# design.net
KiCad netlist of a schematic drawn in EasyEDA Pro
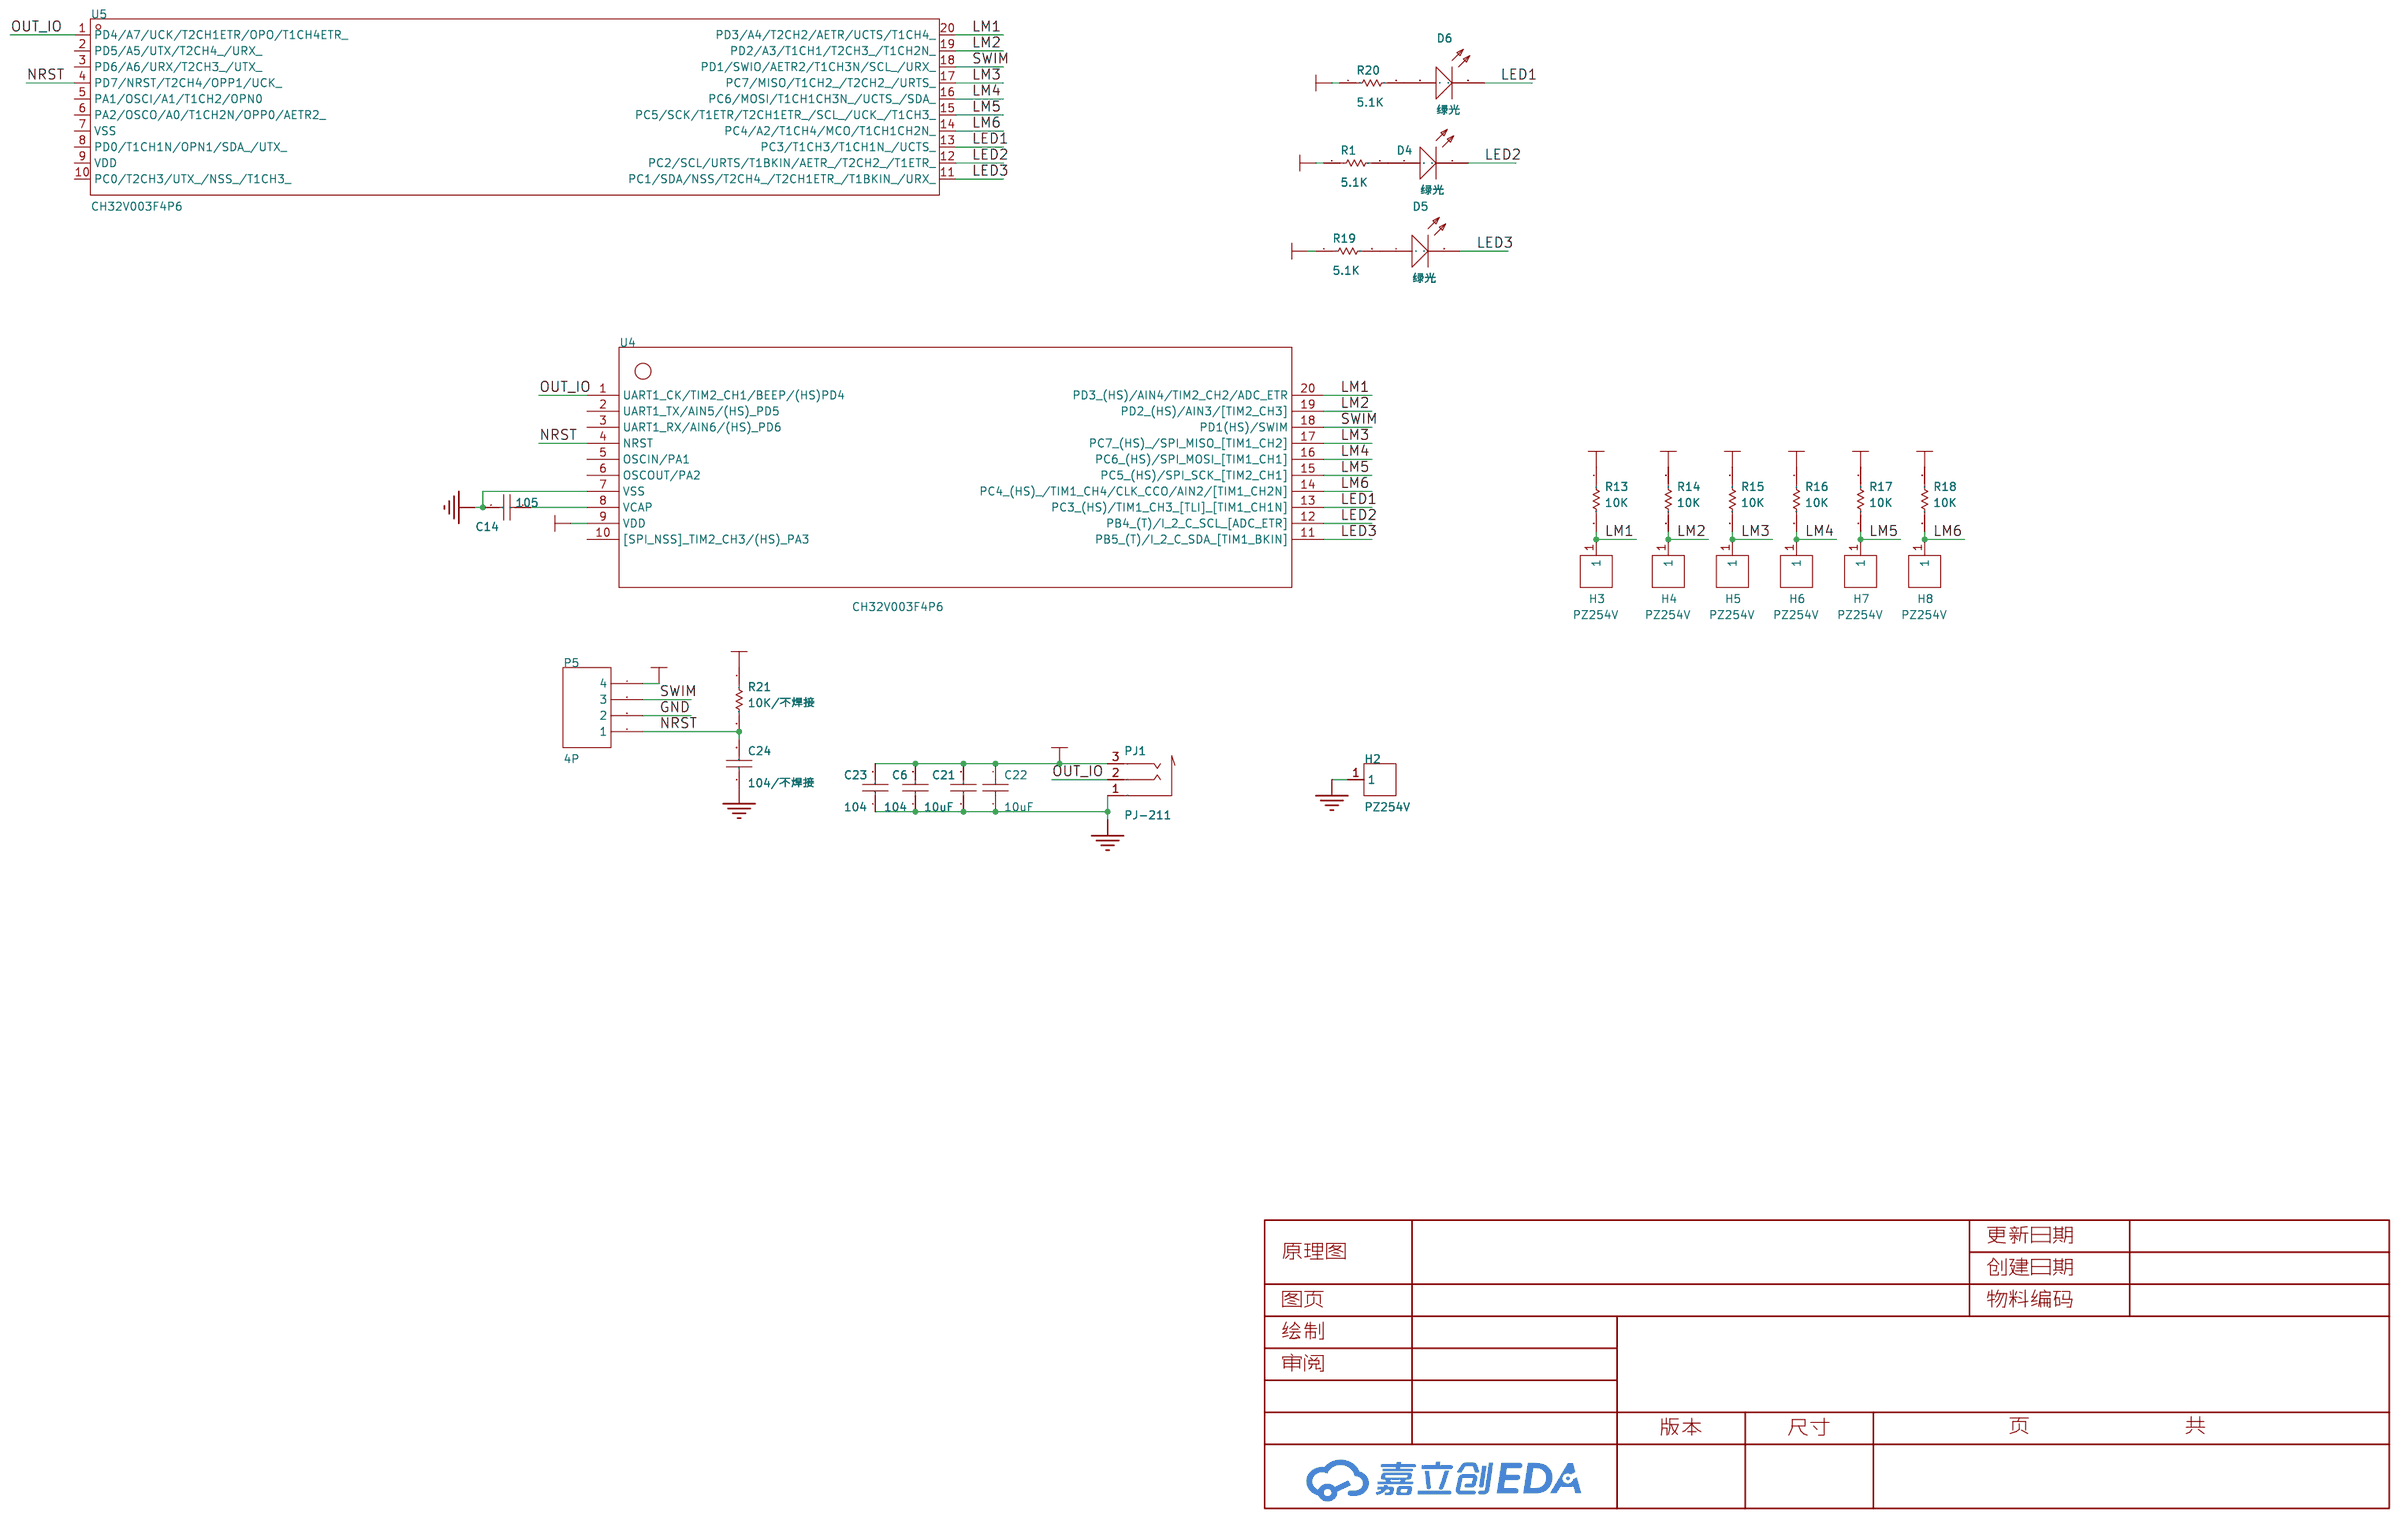
[diagram p0: schematic sheet]

(export (version "E")
  (design (tool "Eeschema 10.0.6"))
  (components
    (comp (ref "C6")
      (value "104")
      (footprint "easyedapro:0603C")
      (description "Capacitor (Semiconductor SIM Model)")
      (libsource (lib "easyedapro") (part "Cap Semi"))
    )
    (comp (ref "C14")
      (value "105")
      (footprint "easyedapro:0603C")
      (description "Capacitor (Semiconductor SIM Model)")
      (libsource (lib "easyedapro") (part "Cap Semi"))
    )
    (comp (ref "C21") (value "10uF") (libsource (lib "easyedapro") (part "CAP")))
    (comp (ref "C22") (value "10uF") (libsource (lib "easyedapro") (part "CAP")))
    (comp (ref "C23")
      (value "104")
      (footprint "easyedapro:0603C")
      (description "Capacitor (Semiconductor SIM Model)")
      (libsource (lib "easyedapro") (part "Cap Semi"))
    )
    (comp (ref "C24")
      (value "104/不焊接")
      (footprint "easyedapro:0603C")
      (description "Capacitor (Semiconductor SIM Model)")
      (libsource (lib "easyedapro") (part "Cap Semi"))
    )
    (comp (ref "D4")
      (value "绿光")
      (footprint "easyedapro:0603LED")
      (libsource (lib "easyedapro") (part "LED"))
    )
    (comp (ref "D5")
      (value "绿光")
      (footprint "easyedapro:0603LED")
      (libsource (lib "easyedapro") (part "LED"))
    )
    (comp (ref "D6")
      (value "绿光")
      (footprint "easyedapro:0603LED")
      (libsource (lib "easyedapro") (part "LED"))
    )
    (comp (ref "H2")
      (value "PZ254V")
      (footprint "easyedapro:HDR-TH_1P-PZ254V-11-01P-YL")
      (description "排针2.54mm间距 直插 1x01位 黄色胶芯")
      (fields (field (name "Manufacturer") "XFCN(兴飞)"))
      (libsource (lib "easyedapro") (part "PZ254V-11-01P-YL"))
    )
    (comp (ref "H3")
      (value "PZ254V")
      (footprint "easyedapro:HDR-TH_1P-PZ254V-11-01P-YL")
      (description "排针2.54mm间距 直插 1x01位 黄色胶芯")
      (fields (field (name "Manufacturer") "XFCN(兴飞)"))
      (libsource (lib "easyedapro") (part "PZ254V-11-01P-YL"))
    )
    (comp (ref "H4")
      (value "PZ254V")
      (footprint "easyedapro:HDR-TH_1P-PZ254V-11-01P-YL")
      (description "排针2.54mm间距 直插 1x01位 黄色胶芯")
      (fields (field (name "Manufacturer") "XFCN(兴飞)"))
      (libsource (lib "easyedapro") (part "PZ254V-11-01P-YL"))
    )
    (comp (ref "H5")
      (value "PZ254V")
      (footprint "easyedapro:HDR-TH_1P-PZ254V-11-01P-YL")
      (description "排针2.54mm间距 直插 1x01位 黄色胶芯")
      (fields (field (name "Manufacturer") "XFCN(兴飞)"))
      (libsource (lib "easyedapro") (part "PZ254V-11-01P-YL"))
    )
    (comp (ref "H6")
      (value "PZ254V")
      (footprint "easyedapro:HDR-TH_1P-PZ254V-11-01P-YL")
      (description "排针2.54mm间距 直插 1x01位 黄色胶芯")
      (fields (field (name "Manufacturer") "XFCN(兴飞)"))
      (libsource (lib "easyedapro") (part "PZ254V-11-01P-YL"))
    )
    (comp (ref "H7")
      (value "PZ254V")
      (footprint "easyedapro:HDR-TH_1P-PZ254V-11-01P-YL")
      (description "排针2.54mm间距 直插 1x01位 黄色胶芯")
      (fields (field (name "Manufacturer") "XFCN(兴飞)"))
      (libsource (lib "easyedapro") (part "PZ254V-11-01P-YL"))
    )
    (comp (ref "H8")
      (value "PZ254V")
      (footprint "easyedapro:HDR-TH_1P-PZ254V-11-01P-YL")
      (description "排针2.54mm间距 直插 1x01位 黄色胶芯")
      (fields (field (name "Manufacturer") "XFCN(兴飞)"))
      (libsource (lib "easyedapro") (part "PZ254V-11-01P-YL"))
    )
    (comp (ref "P5") (value "4P") (libsource (lib "easyedapro") (part "4P")))
    (comp (ref "PJ1")
      (value "PJ-211")
      (footprint "easyedapro:AUDIO-TH_PJ-211")
      (description "连接器类型:2.5mm耳机座;额定电流:500mA;额定电压:30V;触头材质:铜;触头镀层:银;工作温度范围:-30°C~+70°C;")
      (fields (field (name "Manufacturer") "SHOU HAN(首韩)"))
      (libsource (lib "easyedapro") (part "PJ-211"))
    )
    (comp (ref "R1")
      (value "5.1K")
      (footprint "easyedapro:0603R")
      (description "Resistor")
      (libsource (lib "easyedapro") (part "RES"))
    )
    (comp (ref "R13")
      (value "10K")
      (footprint "easyedapro:0603R")
      (description "Resistor")
      (libsource (lib "easyedapro") (part "RES"))
    )
    (comp (ref "R14")
      (value "10K")
      (footprint "easyedapro:0603R")
      (description "Resistor")
      (libsource (lib "easyedapro") (part "RES"))
    )
    (comp (ref "R15")
      (value "10K")
      (footprint "easyedapro:0603R")
      (description "Resistor")
      (libsource (lib "easyedapro") (part "RES"))
    )
    (comp (ref "R16")
      (value "10K")
      (footprint "easyedapro:0603R")
      (description "Resistor")
      (libsource (lib "easyedapro") (part "RES"))
    )
    (comp (ref "R17")
      (value "10K")
      (footprint "easyedapro:0603R")
      (description "Resistor")
      (libsource (lib "easyedapro") (part "RES"))
    )
    (comp (ref "R18")
      (value "10K")
      (footprint "easyedapro:0603R")
      (description "Resistor")
      (libsource (lib "easyedapro") (part "RES"))
    )
    (comp (ref "R19")
      (value "5.1K")
      (footprint "easyedapro:0603R")
      (description "Resistor")
      (libsource (lib "easyedapro") (part "RES"))
    )
    (comp (ref "R20")
      (value "5.1K")
      (footprint "easyedapro:0603R")
      (description "Resistor")
      (libsource (lib "easyedapro") (part "RES"))
    )
    (comp (ref "R21")
      (value "10K/不焊接")
      (footprint "easyedapro:0603R")
      (description "Resistor")
      (libsource (lib "easyedapro") (part "RES"))
    )
    (comp (ref "U4")
      (value "CH32V003F4P6")
      (footprint "easyedapro:TSSOP-20_L6.5-W4.4-P0.65-LS6.4-BL")
      (description "CPU内核:STM8;主频（MAX):16MHz;工作电压:2.95V~ 5.5V;")
      (fields (field (name "Manufacturer") "ST(意法半导体)"))
      (libsource (lib "easyedapro") (part "STM8S003F3P6TR"))
    )
    (comp (ref "U5")
      (value "CH32V003F4P6")
      (footprint "easyedapro:TSSOP-20_L6.5-W4.4-P0.65-LS6.4-BL")
      (fields (field (name "Manufacturer") "WCH(南京沁恒)"))
      (libsource (lib "easyedapro") (part "CH32V003F4P6"))
    )
  )
  (nets
    (net (code "1") (name "/LED1") (class "Default")
      (node (ref "D6") (pin "2") (pinfunction "2_2") (pintype "unspecified"))
      (node (ref "U4") (pin "13") (pinfunction "PC3_(HS)/TIM1_CH3_[TLI]_[TIM1_CH1N]_13") (pintype "input"))
      (node (ref "U5") (pin "13") (pinfunction "PC3/T1CH3/T1CH1N_/UCTS__13") (pintype "unspecified"))
    )
    (net (code "2") (name "/LED2") (class "Default")
      (node (ref "D4") (pin "2") (pinfunction "2_2") (pintype "unspecified"))
      (node (ref "U4") (pin "12") (pinfunction "PB4_(T)/I_2_C_SCL_[ADC_ETR]_12") (pintype "input"))
      (node (ref "U5") (pin "12") (pinfunction "PC2/SCL/URTS/T1BKIN/AETR_/T2CH2_/T1ETR__12") (pintype "unspecified"))
    )
    (net (code "3") (name "/LED3") (class "Default")
      (node (ref "D5") (pin "2") (pinfunction "2_2") (pintype "unspecified"))
      (node (ref "U4") (pin "11") (pinfunction "PB5_(T)/I_2_C_SDA_[TIM1_BKIN]_11") (pintype "input"))
      (node (ref "U5") (pin "11") (pinfunction "PC1/SDA/NSS/T2CH4_/T2CH1ETR_/T1BKIN_/URX__11") (pintype "unspecified"))
    )
    (net (code "4") (name "/LM1") (class "Default")
      (node (ref "H3") (pin "1") (pinfunction "1_1") (pintype "unspecified"))
      (node (ref "R13") (pin "2") (pinfunction "2_2") (pintype "unspecified"))
      (node (ref "U4") (pin "20") (pinfunction "PD3_(HS)/AIN4/TIM2_CH2/ADC_ETR_20") (pintype "input"))
      (node (ref "U5") (pin "20") (pinfunction "PD3/A4/T2CH2/AETR/UCTS/T1CH4__20") (pintype "unspecified"))
    )
    (net (code "5") (name "/LM2") (class "Default")
      (node (ref "H4") (pin "1") (pinfunction "1_1") (pintype "unspecified"))
      (node (ref "R14") (pin "2") (pinfunction "2_2") (pintype "unspecified"))
      (node (ref "U4") (pin "19") (pinfunction "PD2_(HS)/AIN3/[TIM2_CH3]_19") (pintype "input"))
      (node (ref "U5") (pin "19") (pinfunction "PD2/A3/T1CH1/T2CH3_/T1CH2N__19") (pintype "unspecified"))
    )
    (net (code "6") (name "/LM3") (class "Default")
      (node (ref "H5") (pin "1") (pinfunction "1_1") (pintype "unspecified"))
      (node (ref "R15") (pin "2") (pinfunction "2_2") (pintype "unspecified"))
      (node (ref "U4") (pin "17") (pinfunction "PC7_(HS)_/SPI_MISO_[TIM1_CH2]_17") (pintype "input"))
      (node (ref "U5") (pin "17") (pinfunction "PC7/MISO/T1CH2_/T2CH2_/URTS__17") (pintype "unspecified"))
    )
    (net (code "7") (name "/LM4") (class "Default")
      (node (ref "H6") (pin "1") (pinfunction "1_1") (pintype "unspecified"))
      (node (ref "R16") (pin "2") (pinfunction "2_2") (pintype "unspecified"))
      (node (ref "U4") (pin "16") (pinfunction "PC6_(HS)/SPI_MOSI_[TIM1_CH1]_16") (pintype "input"))
      (node (ref "U5") (pin "16") (pinfunction "PC6/MOSI/T1CH1CH3N_/UCTS_/SDA__16") (pintype "unspecified"))
    )
    (net (code "8") (name "/LM5") (class "Default")
      (node (ref "H7") (pin "1") (pinfunction "1_1") (pintype "unspecified"))
      (node (ref "R17") (pin "2") (pinfunction "2_2") (pintype "unspecified"))
      (node (ref "U4") (pin "15") (pinfunction "PC5_(HS)/SPI_SCK_[TIM2_CH1]_15") (pintype "input"))
      (node (ref "U5") (pin "15") (pinfunction "PC5/SCK/T1ETR/T2CH1ETR_/SCL_/UCK_/T1CH3__15") (pintype "unspecified"))
    )
    (net (code "9") (name "/LM6") (class "Default")
      (node (ref "H8") (pin "1") (pinfunction "1_1") (pintype "unspecified"))
      (node (ref "R18") (pin "2") (pinfunction "2_2") (pintype "unspecified"))
      (node (ref "U4") (pin "14") (pinfunction "PC4_(HS)_/TIM1_CH4/CLK_CCO/AIN2/[TIM1_CH2N]_14") (pintype "input"))
      (node (ref "U5") (pin "14") (pinfunction "PC4/A2/T1CH4/MCO/T1CH1CH2N__14") (pintype "unspecified"))
    )
    (net (code "10") (name "/NRST") (class "Default")
      (node (ref "C24") (pin "2") (pinfunction "2_2") (pintype "unspecified"))
      (node (ref "P5") (pin "1") (pinfunction "1_1") (pintype "input"))
      (node (ref "R21") (pin "2") (pinfunction "2_2") (pintype "unspecified"))
      (node (ref "U4") (pin "4") (pinfunction "NRST_4") (pintype "input"))
      (node (ref "U5") (pin "4") (pinfunction "PD7/NRST/T2CH4/OPP1/UCK__4") (pintype "unspecified"))
    )
    (net (code "11") (name "/OUT_IO") (class "Default")
      (node (ref "PJ1") (pin "2") (pinfunction "2_2") (pintype "unspecified"))
      (node (ref "U4") (pin "1") (pinfunction "UART1_CK/TIM2_CH1/BEEP/(HS)PD4_1") (pintype "input"))
      (node (ref "U5") (pin "1") (pinfunction "PD4/A7/UCK/T2CH1ETR/OPO/T1CH4ETR__1") (pintype "unspecified"))
    )
    (net (code "12") (name "/SWIM") (class "Default")
      (node (ref "P5") (pin "3") (pinfunction "3_3") (pintype "input"))
      (node (ref "U4") (pin "18") (pinfunction "PD1(HS)/SWIM_18") (pintype "input"))
      (node (ref "U5") (pin "18") (pinfunction "PD1/SWIO/AETR2/T1CH3N/SCL_/URX__18") (pintype "unspecified"))
    )
    (net (code "13") (name "5V") (class "Default")
      (node (ref "C21") (pin "1") (pinfunction "1_1") (pintype "input"))
      (node (ref "C22") (pin "1") (pinfunction "1_1") (pintype "input"))
      (node (ref "C23") (pin "2") (pinfunction "2_2") (pintype "unspecified"))
      (node (ref "C6") (pin "2") (pinfunction "2_2") (pintype "unspecified"))
      (node (ref "P5") (pin "4") (pinfunction "4_4") (pintype "input"))
      (node (ref "PJ1") (pin "3") (pinfunction "3_3") (pintype "unspecified"))
      (node (ref "R1") (pin "1") (pinfunction "1_1") (pintype "unspecified"))
      (node (ref "R13") (pin "1") (pinfunction "1_1") (pintype "unspecified"))
      (node (ref "R14") (pin "1") (pinfunction "1_1") (pintype "unspecified"))
      (node (ref "R15") (pin "1") (pinfunction "1_1") (pintype "unspecified"))
      (node (ref "R16") (pin "1") (pinfunction "1_1") (pintype "unspecified"))
      (node (ref "R17") (pin "1") (pinfunction "1_1") (pintype "unspecified"))
      (node (ref "R18") (pin "1") (pinfunction "1_1") (pintype "unspecified"))
      (node (ref "R19") (pin "1") (pinfunction "1_1") (pintype "unspecified"))
      (node (ref "R20") (pin "1") (pinfunction "1_1") (pintype "unspecified"))
      (node (ref "R21") (pin "1") (pinfunction "1_1") (pintype "unspecified"))
      (node (ref "U4") (pin "9") (pinfunction "VDD_9") (pintype "input"))
    )
    (net (code "14") (name "GND") (class "Default")
      (node (ref "C14") (pin "2") (pinfunction "2_2") (pintype "unspecified"))
      (node (ref "C21") (pin "2") (pinfunction "2_2") (pintype "input"))
      (node (ref "C22") (pin "2") (pinfunction "2_2") (pintype "input"))
      (node (ref "C23") (pin "1") (pinfunction "1_1") (pintype "unspecified"))
      (node (ref "C24") (pin "1") (pinfunction "1_1") (pintype "unspecified"))
      (node (ref "C6") (pin "1") (pinfunction "1_1") (pintype "unspecified"))
      (node (ref "H2") (pin "1") (pinfunction "1_1") (pintype "unspecified"))
      (node (ref "P5") (pin "2") (pinfunction "2_2") (pintype "input"))
      (node (ref "PJ1") (pin "1") (pinfunction "1_1") (pintype "unspecified"))
      (node (ref "U4") (pin "7") (pinfunction "VSS_7") (pintype "input"))
    )
    (net (code "15") (name "Net-(D4-Pad1)") (class "Default")
      (node (ref "D4") (pin "1") (pinfunction "1_1") (pintype "unspecified"))
      (node (ref "R1") (pin "2") (pinfunction "2_2") (pintype "unspecified"))
    )
    (net (code "16") (name "Net-(D5-Pad1)") (class "Default")
      (node (ref "D5") (pin "1") (pinfunction "1_1") (pintype "unspecified"))
      (node (ref "R19") (pin "2") (pinfunction "2_2") (pintype "unspecified"))
    )
    (net (code "17") (name "Net-(D6-Pad1)") (class "Default")
      (node (ref "D6") (pin "1") (pinfunction "1_1") (pintype "unspecified"))
      (node (ref "R20") (pin "2") (pinfunction "2_2") (pintype "unspecified"))
    )
    (net (code "18") (name "Net-(U4-VCAP)") (class "Default")
      (node (ref "C14") (pin "1") (pinfunction "1_1") (pintype "unspecified"))
      (node (ref "U4") (pin "8") (pinfunction "VCAP_8") (pintype "input"))
    )
    (net (code "19") (name "unconnected-(U4-OSCIN{slash}PA1-Pad5)") (class "Default")
      (node (ref "U4") (pin "5") (pinfunction "OSCIN/PA1_5") (pintype "input"))
    )
    (net (code "20") (name "unconnected-(U4-OSCOUT{slash}PA2-Pad6)") (class "Default")
      (node (ref "U4") (pin "6") (pinfunction "OSCOUT/PA2_6") (pintype "input"))
    )
    (net (code "21") (name "unconnected-(U4-UART1_RX{slash}AIN6{slash}(HS)_PD6-Pad3)") (class "Default")
      (node (ref "U4") (pin "3") (pinfunction "UART1_RX/AIN6/(HS)_PD6_3") (pintype "input"))
    )
    (net (code "22") (name "unconnected-(U4-UART1_TX{slash}AIN5{slash}(HS)_PD5-Pad2)") (class "Default")
      (node (ref "U4") (pin "2") (pinfunction "UART1_TX/AIN5/(HS)_PD5_2") (pintype "input"))
    )
    (net (code "23") (name "unconnected-(U4-[SPI_NSS]_TIM2_CH3{slash}(HS)_PA3-Pad10)") (class "Default")
      (node (ref "U4") (pin "10") (pinfunction "[SPI_NSS]_TIM2_CH3/(HS)_PA3_10") (pintype "input"))
    )
    (net (code "24") (name "unconnected-(U5-PA1{slash}OSCI{slash}A1{slash}T1CH2{slash}OPN0-Pad5)") (class "Default")
      (node (ref "U5") (pin "5") (pinfunction "PA1/OSCI/A1/T1CH2/OPN0_5") (pintype "unspecified"))
    )
    (net (code "25") (name "unconnected-(U5-PA2{slash}OSCO{slash}A0{slash}T1CH2N{slash}OPP0{slash}AETR2_-Pad6)") (class "Default")
      (node (ref "U5") (pin "6") (pinfunction "PA2/OSCO/A0/T1CH2N/OPP0/AETR2__6") (pintype "unspecified"))
    )
    (net (code "26") (name "unconnected-(U5-PC0{slash}T2CH3{slash}UTX_{slash}NSS_{slash}T1CH3_-Pad10)") (class "Default")
      (node (ref "U5") (pin "10") (pinfunction "PC0/T2CH3/UTX_/NSS_/T1CH3__10") (pintype "unspecified"))
    )
    (net (code "27") (name "unconnected-(U5-PD0{slash}T1CH1N{slash}OPN1{slash}SDA_{slash}UTX_-Pad8)") (class "Default")
      (node (ref "U5") (pin "8") (pinfunction "PD0/T1CH1N/OPN1/SDA_/UTX__8") (pintype "unspecified"))
    )
    (net (code "28") (name "unconnected-(U5-PD5{slash}A5{slash}UTX{slash}T2CH4_{slash}URX_-Pad2)") (class "Default")
      (node (ref "U5") (pin "2") (pinfunction "PD5/A5/UTX/T2CH4_/URX__2") (pintype "unspecified"))
    )
    (net (code "29") (name "unconnected-(U5-PD6{slash}A6{slash}URX{slash}T2CH3_{slash}UTX_-Pad3)") (class "Default")
      (node (ref "U5") (pin "3") (pinfunction "PD6/A6/URX/T2CH3_/UTX__3") (pintype "unspecified"))
    )
    (net (code "30") (name "unconnected-(U5-VDD-Pad9)") (class "Default")
      (node (ref "U5") (pin "9") (pinfunction "VDD_9") (pintype "unspecified"))
    )
    (net (code "31") (name "unconnected-(U5-VSS-Pad7)") (class "Default")
      (node (ref "U5") (pin "7") (pinfunction "VSS_7") (pintype "unspecified"))
    )
  )
)
